# PSD_Mount_v6.net
KiCad netlist of a schematic drawn in EAGLE
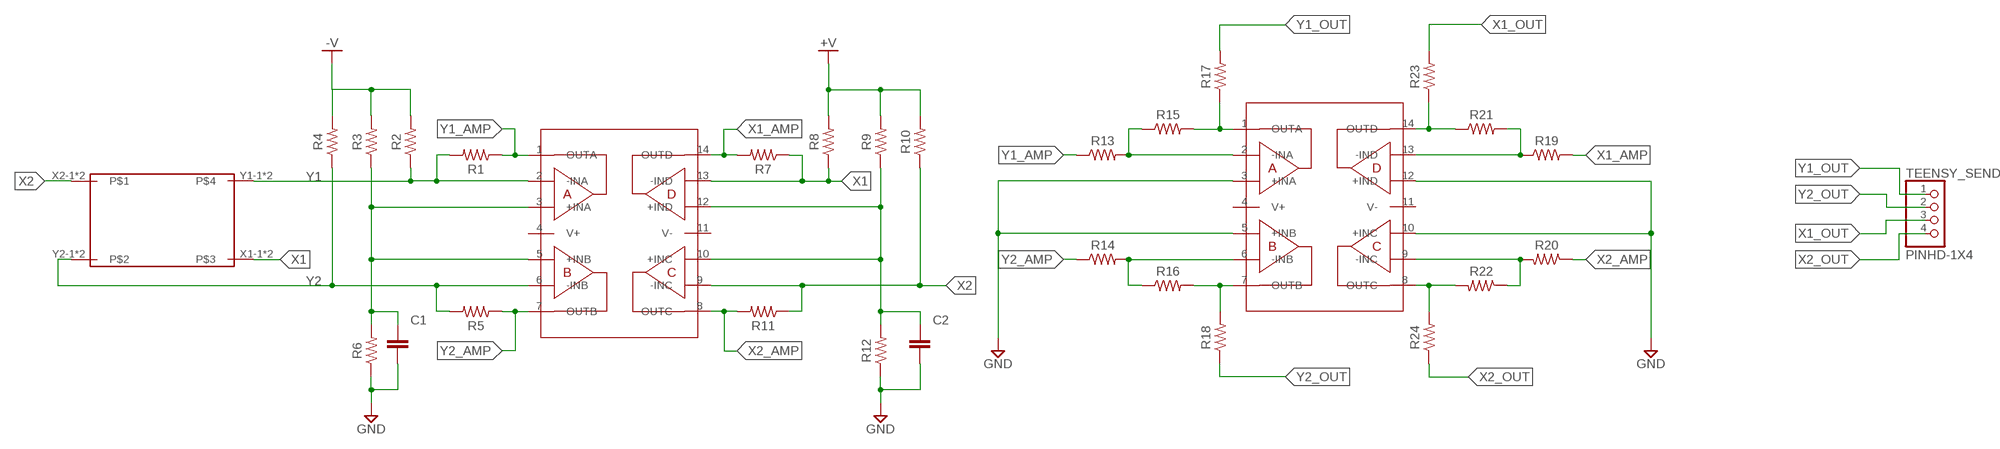
[diagram p0: schematic, sheet 1]

(export (version "E")
  (design (tool "Eeschema 10.0.6"))
  (components
    (comp (ref "C1")
      (value "C_CHIP-0805(2012-METRIC)")
      (footprint "eagle-import:CAPC2012X110")
      (libsource (lib "eagle-import") (part "CCHIP-0805(2012-METRIC)_"))
    )
    (comp (ref "C2")
      (value "C_CHIP-0805(2012-METRIC)")
      (footprint "eagle-import:CAPC2012X110")
      (libsource (lib "eagle-import") (part "CCHIP-0805(2012-METRIC)_"))
    )
    (comp (ref "R1")
      (value "R-US_CHIP-0805(2012-METRIC)")
      (footprint "eagle-import:RESC2012X65")
      (libsource (lib "eagle-import") (part "R-USCHIP-0805(2012-METRIC)_"))
    )
    (comp (ref "R2")
      (value "R-US_CHIP-0805(2012-METRIC)")
      (footprint "eagle-import:RESC2012X65")
      (libsource (lib "eagle-import") (part "R-USCHIP-0805(2012-METRIC)_"))
    )
    (comp (ref "R3")
      (value "R-US_CHIP-0805(2012-METRIC)")
      (footprint "eagle-import:RESC2012X65")
      (libsource (lib "eagle-import") (part "R-USCHIP-0805(2012-METRIC)_"))
    )
    (comp (ref "R4")
      (value "R-US_CHIP-0805(2012-METRIC)")
      (footprint "eagle-import:RESC2012X65")
      (libsource (lib "eagle-import") (part "R-USCHIP-0805(2012-METRIC)_"))
    )
    (comp (ref "R5")
      (value "R-US_CHIP-0805(2012-METRIC)")
      (footprint "eagle-import:RESC2012X65")
      (libsource (lib "eagle-import") (part "R-USCHIP-0805(2012-METRIC)_"))
    )
    (comp (ref "R6")
      (value "R-US_CHIP-0805(2012-METRIC)")
      (footprint "eagle-import:RESC2012X65")
      (libsource (lib "eagle-import") (part "R-USCHIP-0805(2012-METRIC)_"))
    )
    (comp (ref "R7")
      (value "R-US_CHIP-0805(2012-METRIC)")
      (footprint "eagle-import:RESC2012X65")
      (libsource (lib "eagle-import") (part "R-USCHIP-0805(2012-METRIC)_"))
    )
    (comp (ref "R8")
      (value "R-US_CHIP-0805(2012-METRIC)")
      (footprint "eagle-import:RESC2012X65")
      (libsource (lib "eagle-import") (part "R-USCHIP-0805(2012-METRIC)_"))
    )
    (comp (ref "R9")
      (value "R-US_CHIP-0805(2012-METRIC)")
      (footprint "eagle-import:RESC2012X65")
      (libsource (lib "eagle-import") (part "R-USCHIP-0805(2012-METRIC)_"))
    )
    (comp (ref "R10")
      (value "R-US_CHIP-0805(2012-METRIC)")
      (footprint "eagle-import:RESC2012X65")
      (libsource (lib "eagle-import") (part "R-USCHIP-0805(2012-METRIC)_"))
    )
    (comp (ref "R11")
      (value "R-US_CHIP-0805(2012-METRIC)")
      (footprint "eagle-import:RESC2012X65")
      (libsource (lib "eagle-import") (part "R-USCHIP-0805(2012-METRIC)_"))
    )
    (comp (ref "R12")
      (value "R-US_CHIP-0805(2012-METRIC)")
      (footprint "eagle-import:RESC2012X65")
      (libsource (lib "eagle-import") (part "R-USCHIP-0805(2012-METRIC)_"))
    )
    (comp (ref "R13")
      (value "R-US_CHIP-0805(2012-METRIC)")
      (footprint "eagle-import:RESC2012X65")
      (libsource (lib "eagle-import") (part "R-USCHIP-0805(2012-METRIC)_"))
    )
    (comp (ref "R14")
      (value "R-US_CHIP-0805(2012-METRIC)")
      (footprint "eagle-import:RESC2012X65")
      (libsource (lib "eagle-import") (part "R-USCHIP-0805(2012-METRIC)_"))
    )
    (comp (ref "R15")
      (value "R-US_CHIP-0805(2012-METRIC)")
      (footprint "eagle-import:RESC2012X65")
      (libsource (lib "eagle-import") (part "R-USCHIP-0805(2012-METRIC)_"))
    )
    (comp (ref "R16")
      (value "R-US_CHIP-0805(2012-METRIC)")
      (footprint "eagle-import:RESC2012X65")
      (libsource (lib "eagle-import") (part "R-USCHIP-0805(2012-METRIC)_"))
    )
    (comp (ref "R17")
      (value "R-US_CHIP-0805(2012-METRIC)")
      (footprint "eagle-import:RESC2012X65")
      (libsource (lib "eagle-import") (part "R-USCHIP-0805(2012-METRIC)_"))
    )
    (comp (ref "R18")
      (value "R-US_CHIP-0805(2012-METRIC)")
      (footprint "eagle-import:RESC2012X65")
      (libsource (lib "eagle-import") (part "R-USCHIP-0805(2012-METRIC)_"))
    )
    (comp (ref "R19")
      (value "R-US_CHIP-0805(2012-METRIC)")
      (footprint "eagle-import:RESC2012X65")
      (libsource (lib "eagle-import") (part "R-USCHIP-0805(2012-METRIC)_"))
    )
    (comp (ref "R20")
      (value "R-US_CHIP-0805(2012-METRIC)")
      (footprint "eagle-import:RESC2012X65")
      (libsource (lib "eagle-import") (part "R-USCHIP-0805(2012-METRIC)_"))
    )
    (comp (ref "R21")
      (value "R-US_CHIP-0805(2012-METRIC)")
      (footprint "eagle-import:RESC2012X65")
      (libsource (lib "eagle-import") (part "R-USCHIP-0805(2012-METRIC)_"))
    )
    (comp (ref "R22")
      (value "R-US_CHIP-0805(2012-METRIC)")
      (footprint "eagle-import:RESC2012X65")
      (libsource (lib "eagle-import") (part "R-USCHIP-0805(2012-METRIC)_"))
    )
    (comp (ref "R23")
      (value "R-US_CHIP-0805(2012-METRIC)")
      (footprint "eagle-import:RESC2012X65")
      (libsource (lib "eagle-import") (part "R-USCHIP-0805(2012-METRIC)_"))
    )
    (comp (ref "R24")
      (value "R-US_CHIP-0805(2012-METRIC)")
      (footprint "eagle-import:RESC2012X65")
      (libsource (lib "eagle-import") (part "R-USCHIP-0805(2012-METRIC)_"))
    )
    (comp (ref "TEENSY_SEND")
      (value "PINHD-1X4")
      (footprint "eagle-import:1X04")
      (libsource (lib "eagle-import") (part "PINHD-1X4"))
    )
    (comp (ref "U$1")
      (value "2L10UV_SU7")
      (footprint "eagle-import:2L10UV_SU7")
      (libsource (lib "eagle-import") (part "2L10UV_SU7"))
    )
    (comp (ref "U$2")
      (value "OPA4140")
      (footprint "eagle-import:SOP65P640X120-14N")
      (libsource (lib "eagle-import") (part "OPA4140"))
    )
    (comp (ref "U$3")
      (value "OPA4140")
      (footprint "eagle-import:SOP65P640X120-14N")
      (libsource (lib "eagle-import") (part "OPA4140"))
    )
  )
  (nets
    (net (code "1") (name "+V") (class "Default")
      (node (ref "R10") (pin "2") (pinfunction "2_2") (pintype "passive"))
      (node (ref "R8") (pin "2") (pinfunction "2_2") (pintype "passive"))
      (node (ref "R9") (pin "2") (pinfunction "2_2") (pintype "passive"))
    )
    (net (code "2") (name "-V") (class "Default")
      (node (ref "R2") (pin "2") (pinfunction "2_2") (pintype "passive"))
      (node (ref "R3") (pin "2") (pinfunction "2_2") (pintype "passive"))
      (node (ref "R4") (pin "2") (pinfunction "2_2") (pintype "passive"))
    )
    (net (code "3") (name "/Y1") (class "Default")
      (node (ref "R1") (pin "2") (pinfunction "2_2") (pintype "passive"))
      (node (ref "R2") (pin "1") (pinfunction "1_1") (pintype "passive"))
      (node (ref "U$1") (pin "Y1-1") (pinfunction "P$4_Y1-1") (pintype "bidirectional"))
      (node (ref "U$1") (pin "Y1-2") (pinfunction "P$4_Y1-2") (pintype "bidirectional"))
      (node (ref "U$2") (pin "2") (pinfunction "-INA_2") (pintype "bidirectional"))
    )
    (net (code "4") (name "/Y2") (class "Default")
      (node (ref "R4") (pin "1") (pinfunction "1_1") (pintype "passive"))
      (node (ref "R5") (pin "2") (pinfunction "2_2") (pintype "passive"))
      (node (ref "U$1") (pin "Y2-1") (pinfunction "P$2_Y2-1") (pintype "bidirectional"))
      (node (ref "U$1") (pin "Y2-2") (pinfunction "P$2_Y2-2") (pintype "bidirectional"))
      (node (ref "U$2") (pin "6") (pinfunction "-INB_6") (pintype "bidirectional"))
    )
    (net (code "5") (name "GND") (class "Default")
      (node (ref "C1") (pin "2") (pinfunction "2_2") (pintype "passive"))
      (node (ref "C2") (pin "2") (pinfunction "2_2") (pintype "passive"))
      (node (ref "R12") (pin "1") (pinfunction "1_1") (pintype "passive"))
      (node (ref "R6") (pin "1") (pinfunction "1_1") (pintype "passive"))
      (node (ref "U$3") (pin "10") (pinfunction "+INC_10") (pintype "bidirectional"))
      (node (ref "U$3") (pin "12") (pinfunction "+IND_12") (pintype "bidirectional"))
      (node (ref "U$3") (pin "3") (pinfunction "+INA_3") (pintype "bidirectional"))
      (node (ref "U$3") (pin "5") (pinfunction "+INB_5") (pintype "bidirectional"))
    )
    (net (code "6") (name "Net-(U$2-+INA)") (class "Default")
      (node (ref "C1") (pin "1") (pinfunction "1_1") (pintype "passive"))
      (node (ref "R3") (pin "1") (pinfunction "1_1") (pintype "passive"))
      (node (ref "R6") (pin "2") (pinfunction "2_2") (pintype "passive"))
      (node (ref "U$2") (pin "3") (pinfunction "+INA_3") (pintype "bidirectional"))
      (node (ref "U$2") (pin "5") (pinfunction "+INB_5") (pintype "bidirectional"))
    )
    (net (code "7") (name "Net-(U$2-+INC)") (class "Default")
      (node (ref "C2") (pin "1") (pinfunction "1_1") (pintype "passive"))
      (node (ref "R12") (pin "2") (pinfunction "2_2") (pintype "passive"))
      (node (ref "R9") (pin "1") (pinfunction "1_1") (pintype "passive"))
      (node (ref "U$2") (pin "10") (pinfunction "+INC_10") (pintype "bidirectional"))
      (node (ref "U$2") (pin "12") (pinfunction "+IND_12") (pintype "bidirectional"))
    )
    (net (code "8") (name "Net-(U$3--INA)") (class "Default")
      (node (ref "R13") (pin "2") (pinfunction "2_2") (pintype "passive"))
      (node (ref "R15") (pin "1") (pinfunction "1_1") (pintype "passive"))
      (node (ref "U$3") (pin "2") (pinfunction "-INA_2") (pintype "bidirectional"))
    )
    (net (code "9") (name "Net-(U$3--INB)") (class "Default")
      (node (ref "R14") (pin "2") (pinfunction "2_2") (pintype "passive"))
      (node (ref "R16") (pin "1") (pinfunction "1_1") (pintype "passive"))
      (node (ref "U$3") (pin "6") (pinfunction "-INB_6") (pintype "bidirectional"))
    )
    (net (code "10") (name "Net-(U$3--INC)") (class "Default")
      (node (ref "R20") (pin "2") (pinfunction "2_2") (pintype "passive"))
      (node (ref "R22") (pin "1") (pinfunction "1_1") (pintype "passive"))
      (node (ref "U$3") (pin "9") (pinfunction "-INC_9") (pintype "bidirectional"))
    )
    (net (code "11") (name "Net-(U$3--IND)") (class "Default")
      (node (ref "R19") (pin "1") (pinfunction "1_1") (pintype "passive"))
      (node (ref "R21") (pin "2") (pinfunction "2_2") (pintype "passive"))
      (node (ref "U$3") (pin "13") (pinfunction "-IND_13") (pintype "bidirectional"))
    )
    (net (code "12") (name "Net-(U$3-OUTA)") (class "Default")
      (node (ref "R15") (pin "2") (pinfunction "2_2") (pintype "passive"))
      (node (ref "R17") (pin "1") (pinfunction "1_1") (pintype "passive"))
      (node (ref "U$3") (pin "1") (pinfunction "OUTA_1") (pintype "bidirectional"))
    )
    (net (code "13") (name "Net-(U$3-OUTB)") (class "Default")
      (node (ref "R16") (pin "2") (pinfunction "2_2") (pintype "passive"))
      (node (ref "R18") (pin "2") (pinfunction "2_2") (pintype "passive"))
      (node (ref "U$3") (pin "7") (pinfunction "OUTB_7") (pintype "bidirectional"))
    )
    (net (code "14") (name "Net-(U$3-OUTC)") (class "Default")
      (node (ref "R22") (pin "2") (pinfunction "2_2") (pintype "passive"))
      (node (ref "R24") (pin "2") (pinfunction "2_2") (pintype "passive"))
      (node (ref "U$3") (pin "8") (pinfunction "OUTC_8") (pintype "bidirectional"))
    )
    (net (code "15") (name "Net-(U$3-OUTD)") (class "Default")
      (node (ref "R21") (pin "1") (pinfunction "1_1") (pintype "passive"))
      (node (ref "R23") (pin "1") (pinfunction "1_1") (pintype "passive"))
      (node (ref "U$3") (pin "14") (pinfunction "OUTD_14") (pintype "bidirectional"))
    )
    (net (code "16") (name "X1") (class "Default")
      (node (ref "R7") (pin "1") (pinfunction "1_1") (pintype "passive"))
      (node (ref "R8") (pin "1") (pinfunction "1_1") (pintype "passive"))
      (node (ref "U$1") (pin "X1-1") (pinfunction "P$3_X1-1") (pintype "bidirectional"))
      (node (ref "U$1") (pin "X1-2") (pinfunction "P$3_X1-2") (pintype "bidirectional"))
      (node (ref "U$2") (pin "13") (pinfunction "-IND_13") (pintype "bidirectional"))
    )
    (net (code "17") (name "X1_AMP") (class "Default")
      (node (ref "R19") (pin "2") (pinfunction "2_2") (pintype "passive"))
      (node (ref "R7") (pin "2") (pinfunction "2_2") (pintype "passive"))
      (node (ref "U$2") (pin "14") (pinfunction "OUTD_14") (pintype "bidirectional"))
    )
    (net (code "18") (name "X1_OUT") (class "Default")
      (node (ref "R23") (pin "2") (pinfunction "2_2") (pintype "passive"))
      (node (ref "TEENSY_SEND") (pin "3") (pinfunction "3_3") (pintype "passive"))
    )
    (net (code "19") (name "X2") (class "Default")
      (node (ref "R10") (pin "1") (pinfunction "1_1") (pintype "passive"))
      (node (ref "R11") (pin "1") (pinfunction "1_1") (pintype "passive"))
      (node (ref "U$1") (pin "X2-1") (pinfunction "P$1_X2-1") (pintype "bidirectional"))
      (node (ref "U$1") (pin "X2-2") (pinfunction "P$1_X2-2") (pintype "bidirectional"))
      (node (ref "U$2") (pin "9") (pinfunction "-INC_9") (pintype "bidirectional"))
    )
    (net (code "20") (name "X2_AMP") (class "Default")
      (node (ref "R11") (pin "2") (pinfunction "2_2") (pintype "passive"))
      (node (ref "R20") (pin "1") (pinfunction "1_1") (pintype "passive"))
      (node (ref "U$2") (pin "8") (pinfunction "OUTC_8") (pintype "bidirectional"))
    )
    (net (code "21") (name "X2_OUT") (class "Default")
      (node (ref "R24") (pin "1") (pinfunction "1_1") (pintype "passive"))
      (node (ref "TEENSY_SEND") (pin "4") (pinfunction "4_4") (pintype "passive"))
    )
    (net (code "22") (name "Y1_AMP") (class "Default")
      (node (ref "R1") (pin "1") (pinfunction "1_1") (pintype "passive"))
      (node (ref "R13") (pin "1") (pinfunction "1_1") (pintype "passive"))
      (node (ref "U$2") (pin "1") (pinfunction "OUTA_1") (pintype "bidirectional"))
    )
    (net (code "23") (name "Y1_OUT") (class "Default")
      (node (ref "R17") (pin "2") (pinfunction "2_2") (pintype "passive"))
      (node (ref "TEENSY_SEND") (pin "1") (pinfunction "1_1") (pintype "passive"))
    )
    (net (code "24") (name "Y2_AMP") (class "Default")
      (node (ref "R14") (pin "1") (pinfunction "1_1") (pintype "passive"))
      (node (ref "R5") (pin "1") (pinfunction "1_1") (pintype "passive"))
      (node (ref "U$2") (pin "7") (pinfunction "OUTB_7") (pintype "bidirectional"))
    )
    (net (code "25") (name "Y2_OUT") (class "Default")
      (node (ref "R18") (pin "1") (pinfunction "1_1") (pintype "passive"))
      (node (ref "TEENSY_SEND") (pin "2") (pinfunction "2_2") (pintype "passive"))
    )
    (net (code "26") (name "unconnected-(U$2-V+-Pad4)") (class "Default")
      (node (ref "U$2") (pin "4") (pinfunction "V+_4") (pintype "bidirectional"))
    )
    (net (code "27") (name "unconnected-(U$2-V--Pad11)") (class "Default")
      (node (ref "U$2") (pin "11") (pinfunction "V-_11") (pintype "bidirectional"))
    )
    (net (code "28") (name "unconnected-(U$3-V+-Pad4)") (class "Default")
      (node (ref "U$3") (pin "4") (pinfunction "V+_4") (pintype "bidirectional"))
    )
    (net (code "29") (name "unconnected-(U$3-V--Pad11)") (class "Default")
      (node (ref "U$3") (pin "11") (pinfunction "V-_11") (pintype "bidirectional"))
    )
  )
)
